# cascade_sampler_6D.net
KiCad netlist of a schematic drawn in EAGLE
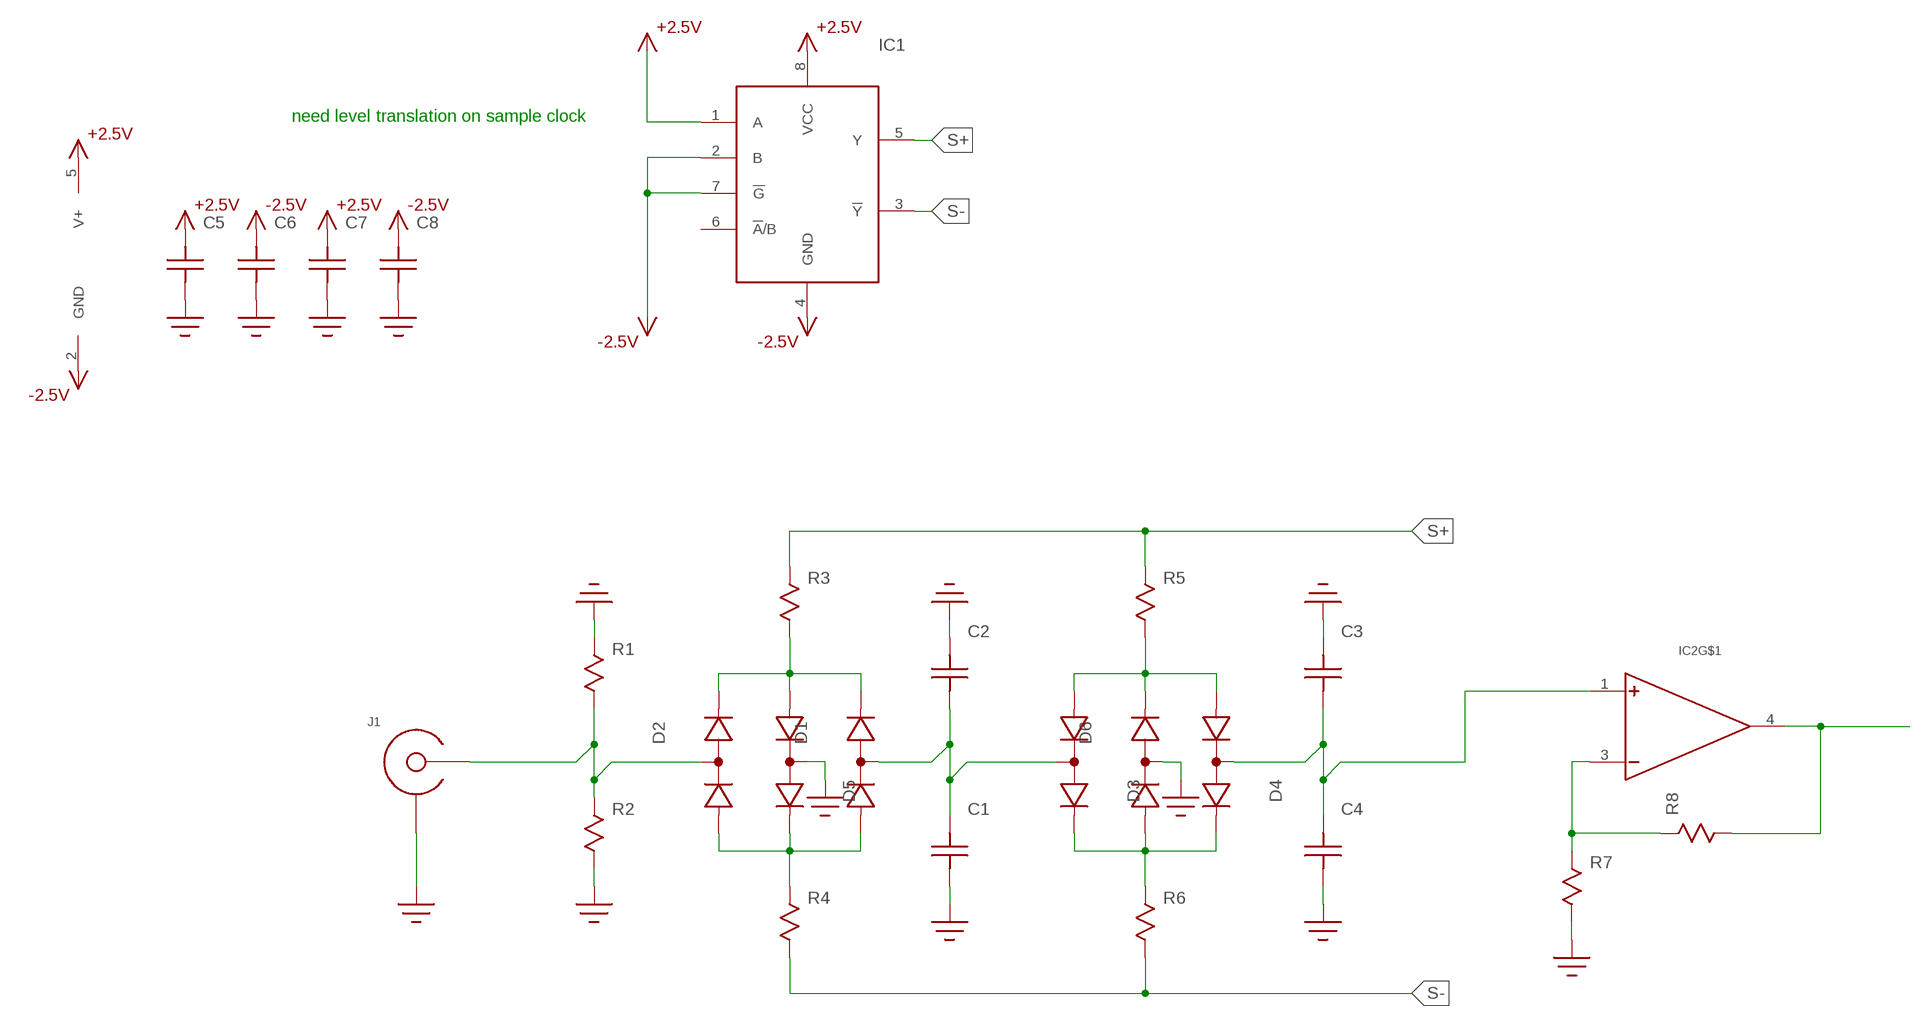
[diagram p0: schematic, sheet 1]

(export (version "E")
  (design (tool "Eeschema 10.0.6"))
  (components
    (comp (ref "C1")
      (value "C0603")
      (footprint "eagle-import:C0603")
      (libsource (lib "eagle-import") (part "C0603"))
    )
    (comp (ref "C2")
      (value "C0603")
      (footprint "eagle-import:C0603")
      (libsource (lib "eagle-import") (part "C0603"))
    )
    (comp (ref "C3")
      (value "C0603")
      (footprint "eagle-import:C0603")
      (libsource (lib "eagle-import") (part "C0603"))
    )
    (comp (ref "C4")
      (value "C0603")
      (footprint "eagle-import:C0603")
      (libsource (lib "eagle-import") (part "C0603"))
    )
    (comp (ref "C5")
      (value "C0603")
      (footprint "eagle-import:C0603")
      (libsource (lib "eagle-import") (part "C0603"))
    )
    (comp (ref "C6")
      (value "C0603")
      (footprint "eagle-import:C0603")
      (libsource (lib "eagle-import") (part "C0603"))
    )
    (comp (ref "C7")
      (value "C0603")
      (footprint "eagle-import:C0603")
      (libsource (lib "eagle-import") (part "C0603"))
    )
    (comp (ref "C8")
      (value "C0603")
      (footprint "eagle-import:C0603")
      (libsource (lib "eagle-import") (part "C0603"))
    )
    (comp (ref "D1")
      (value "MMBD352LT1G")
      (footprint "eagle-import:SOT-23")
      (libsource (lib "eagle-import") (part "MMBD352LT1G"))
    )
    (comp (ref "D2")
      (value "MMBD353LT1G")
      (footprint "eagle-import:SOT-23")
      (libsource (lib "eagle-import") (part "MMBD353LT1G"))
    )
    (comp (ref "D3")
      (value "MMBD352LT1G")
      (footprint "eagle-import:SOT-23")
      (libsource (lib "eagle-import") (part "MMBD352LT1G"))
    )
    (comp (ref "D4")
      (value "MMBD353LT1G")
      (footprint "eagle-import:SOT-23")
      (libsource (lib "eagle-import") (part "MMBD353LT1G"))
    )
    (comp (ref "D5")
      (value "MMBD353LT1G")
      (footprint "eagle-import:SOT-23")
      (libsource (lib "eagle-import") (part "MMBD353LT1G"))
    )
    (comp (ref "D6")
      (value "MMBD352LT1G")
      (footprint "eagle-import:SOT-23")
      (libsource (lib "eagle-import") (part "MMBD352LT1G"))
    )
    (comp (ref "IC1")
      (value "74LVC2G157")
      (footprint "eagle-import:SSOP8")
      (libsource (lib "eagle-import") (part "74LVC2G157"))
    )
    (comp (ref "IC2")
      (value "MCP6V81U")
      (footprint "eagle-import:SOT23-5")
      (libsource (lib "eagle-import") (part "MCP6V81U"))
    )
    (comp (ref "J1")
      (value "EDGE_LAUNCH_JACKNARROW")
      (footprint "eagle-import:EDGE_LAUNCH_RF_CON_NARROW")
      (libsource (lib "eagle-import") (part "EDGE_LAUNCH_JACKNARROW"))
    )
    (comp (ref "R1")
      (value "R0603")
      (footprint "eagle-import:R0603")
      (libsource (lib "eagle-import") (part "R0603"))
    )
    (comp (ref "R2")
      (value "R0603")
      (footprint "eagle-import:R0603")
      (libsource (lib "eagle-import") (part "R0603"))
    )
    (comp (ref "R3")
      (value "R0603")
      (footprint "eagle-import:R0603")
      (libsource (lib "eagle-import") (part "R0603"))
    )
    (comp (ref "R4")
      (value "R0603")
      (footprint "eagle-import:R0603")
      (libsource (lib "eagle-import") (part "R0603"))
    )
    (comp (ref "R5")
      (value "R0603")
      (footprint "eagle-import:R0603")
      (libsource (lib "eagle-import") (part "R0603"))
    )
    (comp (ref "R6")
      (value "R0603")
      (footprint "eagle-import:R0603")
      (libsource (lib "eagle-import") (part "R0603"))
    )
    (comp (ref "R7")
      (value "R0603")
      (footprint "eagle-import:R0603")
      (libsource (lib "eagle-import") (part "R0603"))
    )
    (comp (ref "R8")
      (value "R0603")
      (footprint "eagle-import:R0603")
      (libsource (lib "eagle-import") (part "R0603"))
    )
  )
  (nets
    (net (code "1") (name "+2.5V") (class "Default")
      (node (ref "C5") (pin "P$2") (pinfunction "P$2_P$2") (pintype "bidirectional"))
      (node (ref "C7") (pin "P$2") (pinfunction "P$2_P$2") (pintype "bidirectional"))
      (node (ref "IC1") (pin "1") (pinfunction "A_1") (pintype "bidirectional"))
      (node (ref "IC1") (pin "8") (pinfunction "VCC_8") (pintype "bidirectional"))
      (node (ref "IC2") (pin "5") (pinfunction "V+_5") (pintype "bidirectional"))
    )
    (net (code "2") (name "-2.5V") (class "Default")
      (node (ref "C6") (pin "P$2") (pinfunction "P$2_P$2") (pintype "bidirectional"))
      (node (ref "C8") (pin "P$2") (pinfunction "P$2_P$2") (pintype "bidirectional"))
      (node (ref "IC1") (pin "2") (pinfunction "B_2") (pintype "bidirectional"))
      (node (ref "IC1") (pin "4") (pinfunction "GND_4") (pintype "bidirectional"))
      (node (ref "IC1") (pin "7") (pinfunction "~{G}_7") (pintype "bidirectional"))
      (node (ref "IC2") (pin "2") (pinfunction "GND_2") (pintype "bidirectional"))
    )
    (net (code "3") (name "GND") (class "Default")
      (node (ref "C1") (pin "P$1") (pinfunction "P$1_P$1") (pintype "bidirectional"))
      (node (ref "C2") (pin "P$2") (pinfunction "P$2_P$2") (pintype "bidirectional"))
      (node (ref "C3") (pin "P$2") (pinfunction "P$2_P$2") (pintype "bidirectional"))
      (node (ref "C4") (pin "P$1") (pinfunction "P$1_P$1") (pintype "bidirectional"))
      (node (ref "C5") (pin "P$1") (pinfunction "P$1_P$1") (pintype "bidirectional"))
      (node (ref "C6") (pin "P$1") (pinfunction "P$1_P$1") (pintype "bidirectional"))
      (node (ref "C7") (pin "P$1") (pinfunction "P$1_P$1") (pintype "bidirectional"))
      (node (ref "C8") (pin "P$1") (pinfunction "P$1_P$1") (pintype "bidirectional"))
      (node (ref "D5") (pin "3") (pinfunction "COMMON_3") (pintype "bidirectional"))
      (node (ref "D6") (pin "3") (pinfunction "COMMON_3") (pintype "bidirectional"))
      (node (ref "J1") (pin "GND@1") (pinfunction "SHIELD_GND@1") (pintype "bidirectional"))
      (node (ref "J1") (pin "GND@2") (pinfunction "SHIELD_GND@2") (pintype "bidirectional"))
      (node (ref "J1") (pin "GND@3") (pinfunction "SHIELD_GND@3") (pintype "bidirectional"))
      (node (ref "J1") (pin "GND@4") (pinfunction "SHIELD_GND@4") (pintype "bidirectional"))
      (node (ref "J1") (pin "GND@5") (pinfunction "SHIELD_GND@5") (pintype "bidirectional"))
      (node (ref "J1") (pin "GND@6") (pinfunction "SHIELD_GND@6") (pintype "bidirectional"))
      (node (ref "J1") (pin "SHIELD@1") (pinfunction "SHIELD_SHIELD@1") (pintype "bidirectional"))
      (node (ref "J1") (pin "SHIELD@2") (pinfunction "SHIELD_SHIELD@2") (pintype "bidirectional"))
      (node (ref "R1") (pin "P$1") (pinfunction "P$3_P$1") (pintype "bidirectional"))
      (node (ref "R2") (pin "P$2") (pinfunction "P$4_P$2") (pintype "bidirectional"))
      (node (ref "R7") (pin "P$2") (pinfunction "P$4_P$2") (pintype "bidirectional"))
    )
    (net (code "4") (name "Net-(D1-ANODE)") (class "Default")
      (node (ref "D1") (pin "1") (pinfunction "ANODE_1") (pintype "bidirectional"))
      (node (ref "D2") (pin "2") (pinfunction "ANODE_2") (pintype "bidirectional"))
      (node (ref "D5") (pin "1") (pinfunction "CATHODE_1") (pintype "bidirectional"))
      (node (ref "R4") (pin "P$1") (pinfunction "P$3_P$1") (pintype "bidirectional"))
    )
    (net (code "5") (name "Net-(D1-CATHODE)") (class "Default")
      (node (ref "D1") (pin "2") (pinfunction "CATHODE_2") (pintype "bidirectional"))
      (node (ref "D2") (pin "1") (pinfunction "CATHODE_1") (pintype "bidirectional"))
      (node (ref "D5") (pin "2") (pinfunction "ANODE_2") (pintype "bidirectional"))
      (node (ref "R3") (pin "P$2") (pinfunction "P$4_P$2") (pintype "bidirectional"))
    )
    (net (code "6") (name "Net-(D1-COMMON)") (class "Default")
      (node (ref "C1") (pin "P$2") (pinfunction "P$2_P$2") (pintype "bidirectional"))
      (node (ref "C2") (pin "P$1") (pinfunction "P$1_P$1") (pintype "bidirectional"))
      (node (ref "D1") (pin "3") (pinfunction "COMMON_3") (pintype "bidirectional"))
      (node (ref "D3") (pin "3") (pinfunction "COMMON_3") (pintype "bidirectional"))
    )
    (net (code "7") (name "Net-(D2-COMMON)") (class "Default")
      (node (ref "D2") (pin "3") (pinfunction "COMMON_3") (pintype "bidirectional"))
      (node (ref "J1") (pin "CENTER") (pinfunction "CENTER_CENTER") (pintype "bidirectional"))
      (node (ref "R1") (pin "P$2") (pinfunction "P$4_P$2") (pintype "bidirectional"))
      (node (ref "R2") (pin "P$1") (pinfunction "P$3_P$1") (pintype "bidirectional"))
    )
    (net (code "8") (name "Net-(D3-ANODE)") (class "Default")
      (node (ref "D3") (pin "1") (pinfunction "ANODE_1") (pintype "bidirectional"))
      (node (ref "D4") (pin "2") (pinfunction "ANODE_2") (pintype "bidirectional"))
      (node (ref "D6") (pin "2") (pinfunction "CATHODE_2") (pintype "bidirectional"))
      (node (ref "R5") (pin "P$2") (pinfunction "P$4_P$2") (pintype "bidirectional"))
    )
    (net (code "9") (name "Net-(D3-CATHODE)") (class "Default")
      (node (ref "D3") (pin "2") (pinfunction "CATHODE_2") (pintype "bidirectional"))
      (node (ref "D4") (pin "1") (pinfunction "CATHODE_1") (pintype "bidirectional"))
      (node (ref "D6") (pin "1") (pinfunction "ANODE_1") (pintype "bidirectional"))
      (node (ref "R6") (pin "P$1") (pinfunction "P$3_P$1") (pintype "bidirectional"))
    )
    (net (code "10") (name "Net-(D4-COMMON)") (class "Default")
      (node (ref "C3") (pin "P$1") (pinfunction "P$1_P$1") (pintype "bidirectional"))
      (node (ref "C4") (pin "P$2") (pinfunction "P$2_P$2") (pintype "bidirectional"))
      (node (ref "D4") (pin "3") (pinfunction "COMMON_3") (pintype "bidirectional"))
      (node (ref "IC2") (pin "1") (pinfunction "+_1") (pintype "bidirectional"))
    )
    (net (code "11") (name "Net-(IC2A--)") (class "Default")
      (node (ref "IC2") (pin "3") (pinfunction "-_3") (pintype "bidirectional"))
      (node (ref "R7") (pin "P$1") (pinfunction "P$3_P$1") (pintype "bidirectional"))
      (node (ref "R8") (pin "P$1") (pinfunction "P$3_P$1") (pintype "bidirectional"))
    )
    (net (code "12") (name "Net-(IC2A-OUT)") (class "Default")
      (node (ref "IC2") (pin "4") (pinfunction "OUT_4") (pintype "bidirectional"))
      (node (ref "R8") (pin "P$2") (pinfunction "P$4_P$2") (pintype "bidirectional"))
    )
    (net (code "13") (name "S+") (class "Default")
      (node (ref "IC1") (pin "5") (pinfunction "Y_5") (pintype "bidirectional"))
      (node (ref "R3") (pin "P$1") (pinfunction "P$3_P$1") (pintype "bidirectional"))
      (node (ref "R5") (pin "P$1") (pinfunction "P$3_P$1") (pintype "bidirectional"))
    )
    (net (code "14") (name "S-") (class "Default")
      (node (ref "IC1") (pin "3") (pinfunction "~{Y}_3") (pintype "bidirectional"))
      (node (ref "R4") (pin "P$2") (pinfunction "P$4_P$2") (pintype "bidirectional"))
      (node (ref "R6") (pin "P$2") (pinfunction "P$4_P$2") (pintype "bidirectional"))
    )
    (net (code "15") (name "unconnected-(IC1-~{A}{slash}B-Pad6)") (class "Default")
      (node (ref "IC1") (pin "6") (pinfunction "~{A}/B_6") (pintype "bidirectional"))
    )
  )
)
